# BMS029B_PinConfig.net
KiCad netlist of a schematic drawn in Altium Designer
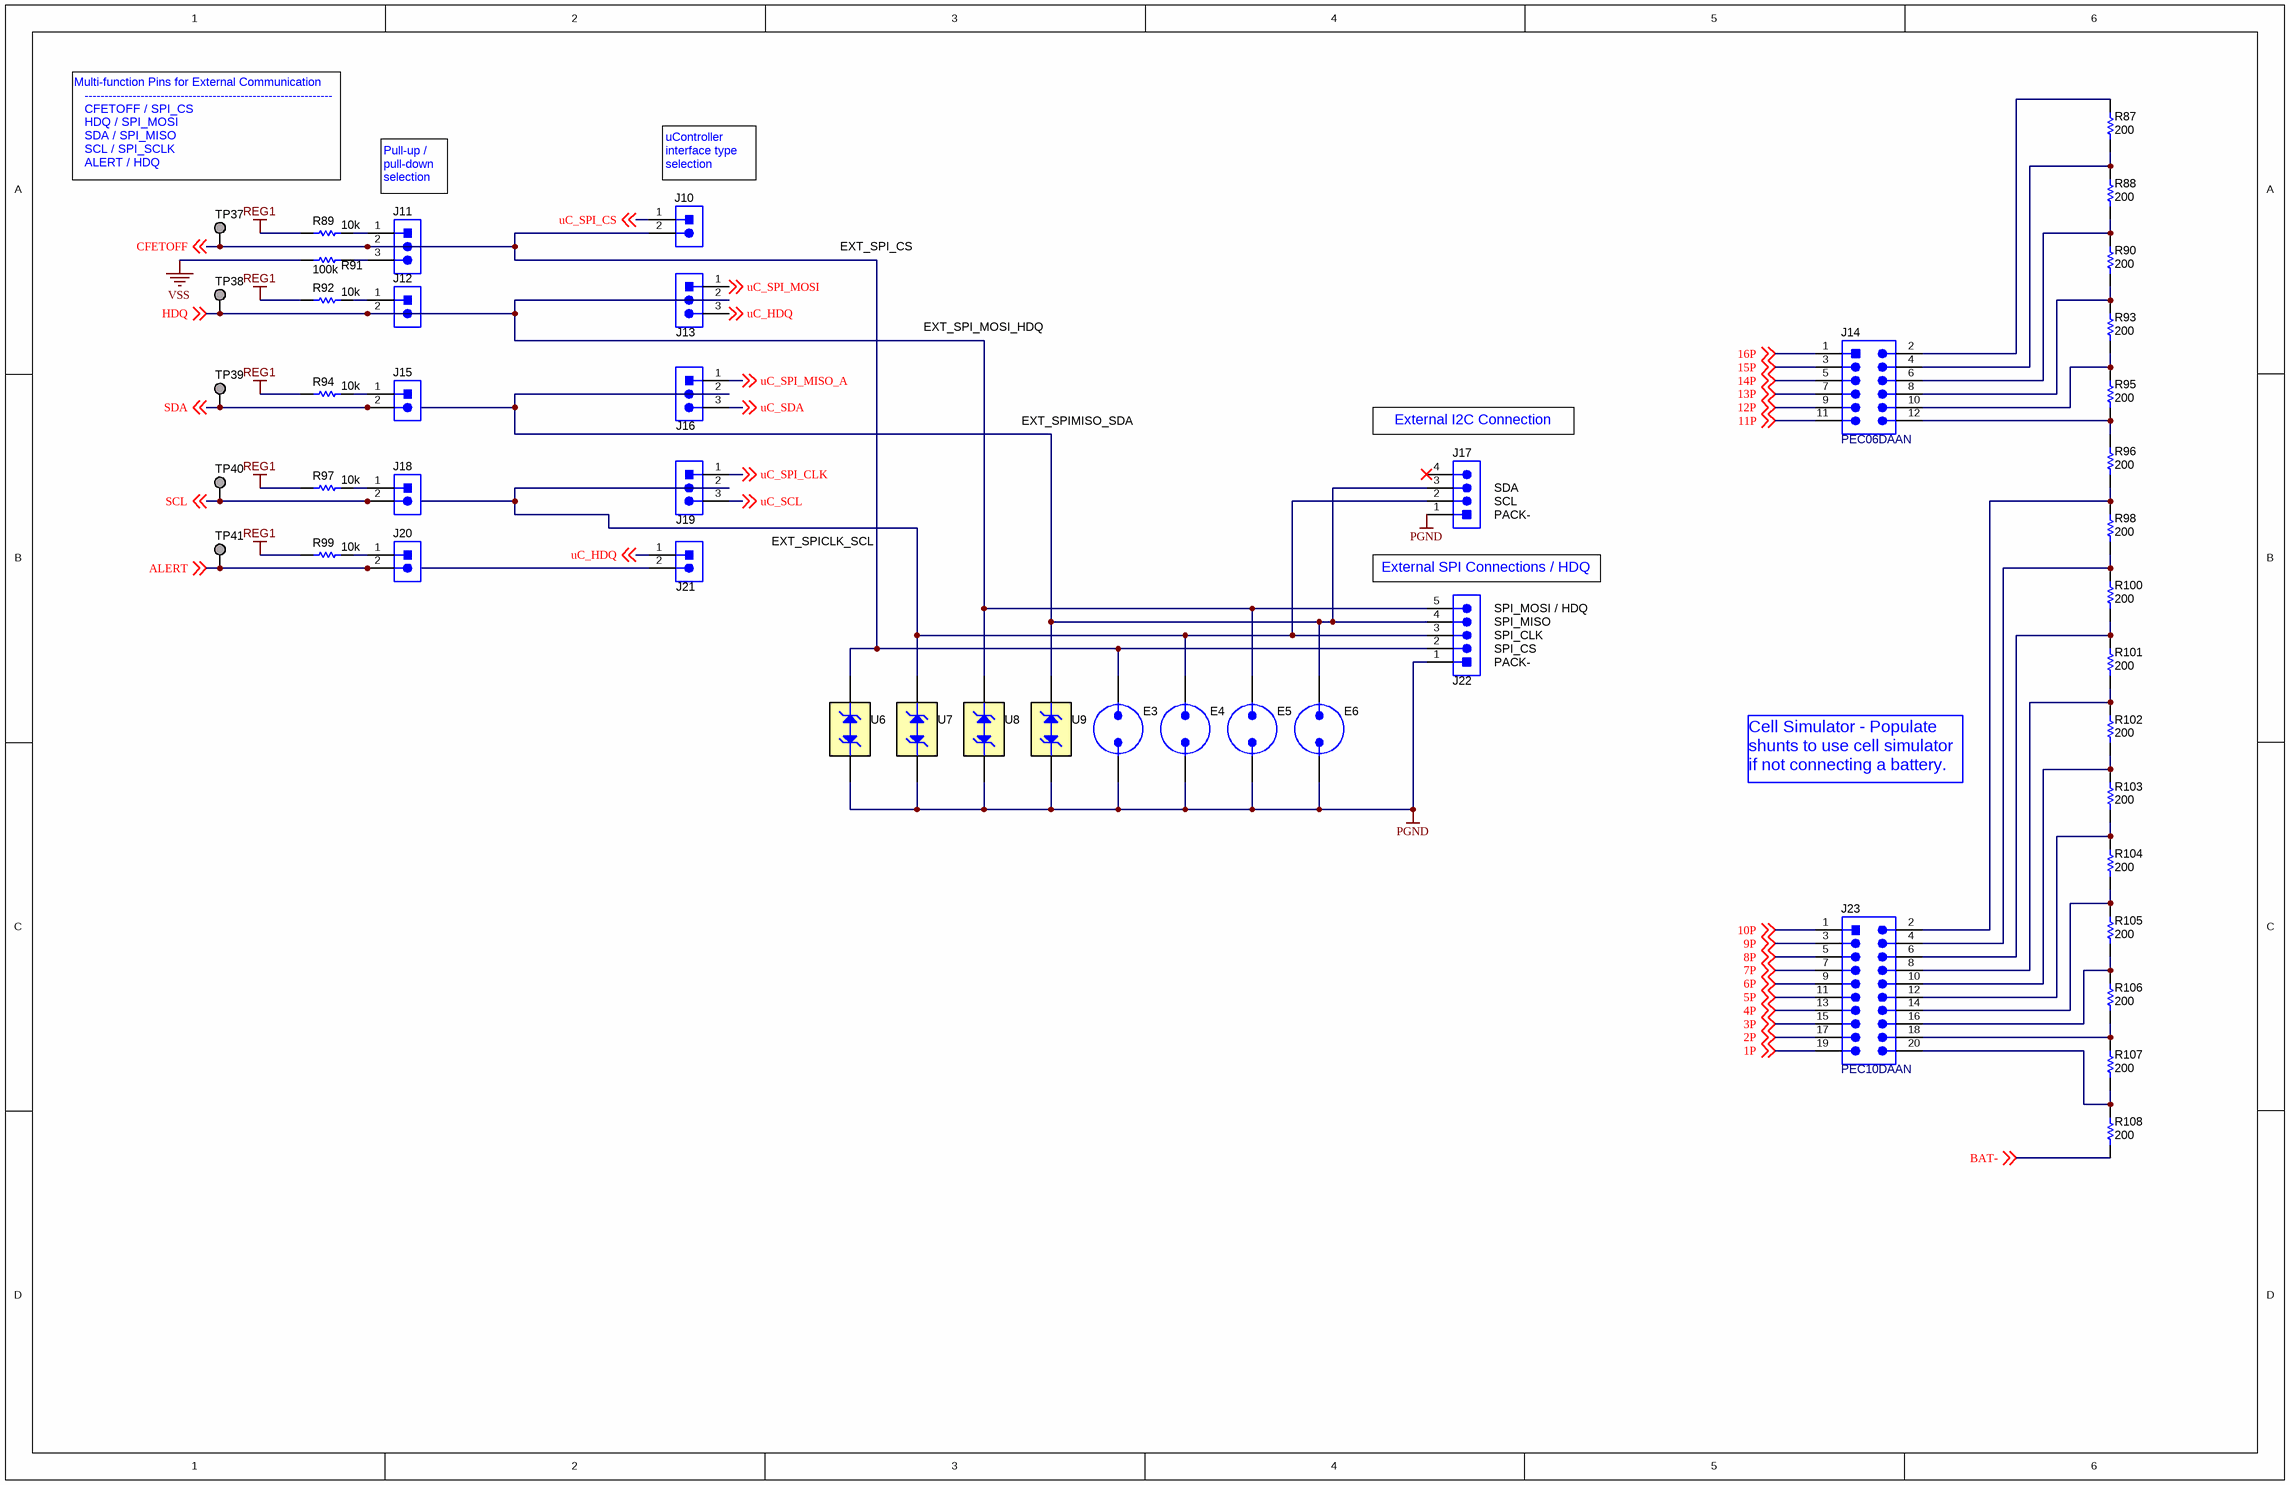
[diagram p0: BMS029B_PinConfig.SchDoc]

(export (version "E")
  (design (tool "Eeschema 10.0.6"))
  (components
    (comp (ref "E3")
      (value "Spark Gap")
      (footprint "SPARK_GAP2")
      (libsource (lib "Altium Vault - TI") (part "CMP-0079939-1"))
    )
    (comp (ref "E4")
      (value "Spark Gap")
      (footprint "SPARK_GAP2")
      (libsource (lib "Altium Vault - TI") (part "CMP-0079939-1"))
    )
    (comp (ref "E5")
      (value "Spark Gap")
      (footprint "SPARK_GAP2")
      (libsource (lib "Altium Vault - TI") (part "CMP-0079939-1"))
    )
    (comp (ref "E6")
      (value "Spark Gap")
      (footprint "SPARK_GAP2")
      (libsource (lib "Altium Vault - TI") (part "CMP-0079939-1"))
    )
    (comp (ref "J10")
      (value "PEC02SAAN")
      (footprint "CONN_PEC02SAAN")
      (description "Header, 100mil, 2x1, Tin, TH")
      (fields
        (field (name "MANUFACTURER") "Sullins Connector Solutions")
        (field (name "PUBLISHER") "Texas Instruments")
      )
      (libsource (lib "Altium Vault - TI") (part "Header_2x1"))
    )
    (comp (ref "J11")
      (value "87898-0304")
      (footprint "Molex_87898-0304")
      (description "Header, 2.54mm, 3x1, Gold, SMT")
      (fields (field (name "MANUFACTURER") "Molex") (field (name "PUBLISHER") "Texas Instruments"))
      (libsource (lib "") (part "CMP-0075388-1_1"))
    )
    (comp (ref "J12")
      (value "PEC02SAAN")
      (footprint "CONN_PEC02SAAN")
      (description "Header, 100mil, 2x1, Tin, TH")
      (fields
        (field (name "MANUFACTURER") "Sullins Connector Solutions")
        (field (name "PUBLISHER") "Texas Instruments")
      )
      (libsource (lib "Altium Vault - TI") (part "Header_2x1"))
    )
    (comp (ref "J13")
      (value "87898-0304")
      (footprint "Molex_87898-0304")
      (description "Header, 2.54mm, 3x1, Gold, SMT")
      (fields (field (name "MANUFACTURER") "Molex") (field (name "PUBLISHER") "Texas Instruments"))
      (libsource (lib "Altium Vault - TI") (part "CMP-0075388-1"))
    )
    (comp (ref "J14")
      (value "PEC06DAAN")
      (footprint "CONN_PEC06DAAN")
      (description "Header, 100mil, 6x2, Tin, TH")
      (fields (field (name "MANUFACTURER") "Sullins Connector Solutions"))
      (libsource (lib "Altium Vault - TI") (part "Header_6x2"))
    )
    (comp (ref "J15")
      (value "PEC02SAAN")
      (footprint "CONN_PEC02SAAN")
      (description "Header, 100mil, 2x1, Tin, TH")
      (fields
        (field (name "MANUFACTURER") "Sullins Connector Solutions")
        (field (name "PUBLISHER") "Texas Instruments")
      )
      (libsource (lib "Altium Vault - TI") (part "Header_2x1"))
    )
    (comp (ref "J16")
      (value "87898-0304")
      (footprint "Molex_87898-0304")
      (description "Header, 2.54mm, 3x1, Gold, SMT")
      (fields (field (name "MANUFACTURER") "Molex") (field (name "PUBLISHER") "Texas Instruments"))
      (libsource (lib "Altium Vault - TI") (part "CMP-0075388-1"))
    )
    (comp (ref "J17")
      (value "22/05/3041")
      (footprint "CONN_22-05-3041")
      (description "Header (friction lock), 100mil, 4x1, R/A, TH")
      (fields (field (name "MANUFACTURER") "Molex") (field (name "PUBLISHER") "Texas Instruments"))
      (libsource (lib "Altium Vault - TI") (part "CMP-0055187-1"))
    )
    (comp (ref "J18")
      (value "PEC02SAAN")
      (footprint "CONN_PEC02SAAN")
      (description "Header, 100mil, 2x1, Tin, TH")
      (fields
        (field (name "MANUFACTURER") "Sullins Connector Solutions")
        (field (name "PUBLISHER") "Texas Instruments")
      )
      (libsource (lib "Altium Vault - TI") (part "Header_2x1"))
    )
    (comp (ref "J19")
      (value "87898-0304")
      (footprint "Molex_87898-0304")
      (description "Header, 2.54mm, 3x1, Gold, SMT")
      (fields (field (name "MANUFACTURER") "Molex") (field (name "PUBLISHER") "Texas Instruments"))
      (libsource (lib "Altium Vault - TI") (part "CMP-0075388-1"))
    )
    (comp (ref "J20")
      (value "PEC02SAAN")
      (footprint "CONN_PEC02SAAN")
      (description "Header, 100mil, 2x1, Tin, TH")
      (fields
        (field (name "MANUFACTURER") "Sullins Connector Solutions")
        (field (name "PUBLISHER") "Texas Instruments")
      )
      (libsource (lib "Altium Vault - TI") (part "Header_2x1"))
    )
    (comp (ref "J21")
      (value "PEC02SAAN")
      (footprint "CONN_PEC02SAAN")
      (description "Header, 100mil, 2x1, Tin, TH")
      (fields
        (field (name "MANUFACTURER") "Sullins Connector Solutions")
        (field (name "PUBLISHER") "Texas Instruments")
      )
      (libsource (lib "Altium Vault - TI") (part "Header_2x1"))
    )
    (comp (ref "J22")
      (value "PEC05SAAN")
      (footprint "Sullins_PxC05SAAN")
      (description "Header, 2.54mm, 5x1, Tin, TH")
      (fields
        (field (name "MANUFACTURER") "Sullins Connector Solutions")
        (field (name "PUBLISHER") "Texas Instruments")
      )
      (libsource (lib "Altium Vault - TI") (part "CMP-0054597-1"))
    )
    (comp (ref "J23")
      (value "PEC10DAAN")
      (footprint "SULLINS_PEC10DAAN")
      (description "Header, 2.54mm, 10x2, Tin, TH")
      (fields (field (name "MANUFACTURER") "Sullins Connector Solutions"))
      (libsource (lib "Altium Vault - TI") (part "Header_10x2"))
    )
    (comp (ref "R87")
      (value "CRCW1206200RFKEA")
      (footprint "1206")
      (description "RES, 200, 1%, 0.25 W, AEC-Q200 Grade 0, 1206")
      (fields (field (name "MANUFACTURER") "Vishay-Dale") (field (name "VALUEDISPLAYED") "200"))
      (libsource (lib "Altium Vault - TI") (part "Resistor"))
    )
    (comp (ref "R88")
      (value "CRCW1206200RFKEA")
      (footprint "1206")
      (description "RES, 200, 1%, 0.25 W, AEC-Q200 Grade 0, 1206")
      (fields (field (name "MANUFACTURER") "Vishay-Dale") (field (name "VALUEDISPLAYED") "200"))
      (libsource (lib "Altium Vault - TI") (part "Resistor"))
    )
    (comp (ref "R89")
      (value "CRCW060310K0JNEA")
      (footprint "0603")
      (description "RES, 10 k, 5%, 0.1 W, AEC-Q200 Grade 0, 0603")
      (fields (field (name "MANUFACTURER") "Vishay-Dale") (field (name "VALUEDISPLAYED") "10k"))
      (libsource (lib "Altium Vault - TI") (part "CMP-0025701-4"))
    )
    (comp (ref "R90")
      (value "CRCW1206200RFKEA")
      (footprint "1206")
      (description "RES, 200, 1%, 0.25 W, AEC-Q200 Grade 0, 1206")
      (fields (field (name "MANUFACTURER") "Vishay-Dale") (field (name "VALUEDISPLAYED") "200"))
      (libsource (lib "Altium Vault - TI") (part "Resistor"))
    )
    (comp (ref "R91")
      (value "CRCW0603100KJNEA")
      (footprint "0603")
      (description "RES, 100 k, 5%, 0.1 W, AEC-Q200 Grade 0, 0603")
      (fields (field (name "MANUFACTURER") "Vishay-Dale") (field (name "VALUEDISPLAYED") "100k"))
      (libsource (lib "Altium Vault - TI") (part "Resistor"))
    )
    (comp (ref "R92")
      (value "CRCW060310K0JNEA")
      (footprint "0603")
      (description "RES, 10 k, 5%, 0.1 W, AEC-Q200 Grade 0, 0603")
      (fields (field (name "MANUFACTURER") "Vishay-Dale") (field (name "VALUEDISPLAYED") "10k"))
      (libsource (lib "Altium Vault - TI") (part "CMP-0025701-4"))
    )
    (comp (ref "R93")
      (value "CRCW1206200RFKEA")
      (footprint "1206")
      (description "RES, 200, 1%, 0.25 W, AEC-Q200 Grade 0, 1206")
      (fields (field (name "MANUFACTURER") "Vishay-Dale") (field (name "VALUEDISPLAYED") "200"))
      (libsource (lib "Altium Vault - TI") (part "Resistor"))
    )
    (comp (ref "R94")
      (value "CRCW060310K0JNEA")
      (footprint "0603")
      (description "RES, 10 k, 5%, 0.1 W, AEC-Q200 Grade 0, 0603")
      (fields (field (name "MANUFACTURER") "Vishay-Dale") (field (name "VALUEDISPLAYED") "10k"))
      (libsource (lib "Altium Vault - TI") (part "CMP-0025701-4"))
    )
    (comp (ref "R95")
      (value "CRCW1206200RFKEA")
      (footprint "1206")
      (description "RES, 200, 1%, 0.25 W, AEC-Q200 Grade 0, 1206")
      (fields (field (name "MANUFACTURER") "Vishay-Dale") (field (name "VALUEDISPLAYED") "200"))
      (libsource (lib "Altium Vault - TI") (part "Resistor"))
    )
    (comp (ref "R96")
      (value "CRCW1206200RFKEA")
      (footprint "1206")
      (description "RES, 200, 1%, 0.25 W, AEC-Q200 Grade 0, 1206")
      (fields (field (name "MANUFACTURER") "Vishay-Dale") (field (name "VALUEDISPLAYED") "200"))
      (libsource (lib "Altium Vault - TI") (part "Resistor"))
    )
    (comp (ref "R97")
      (value "CRCW060310K0JNEA")
      (footprint "0603")
      (description "RES, 10 k, 5%, 0.1 W, AEC-Q200 Grade 0, 0603")
      (fields (field (name "MANUFACTURER") "Vishay-Dale") (field (name "VALUEDISPLAYED") "10k"))
      (libsource (lib "Altium Vault - TI") (part "CMP-0025701-4"))
    )
    (comp (ref "R98")
      (value "CRCW1206200RFKEA")
      (footprint "1206")
      (description "RES, 200, 1%, 0.25 W, AEC-Q200 Grade 0, 1206")
      (fields (field (name "MANUFACTURER") "Vishay-Dale") (field (name "VALUEDISPLAYED") "200"))
      (libsource (lib "Altium Vault - TI") (part "Resistor"))
    )
    (comp (ref "R99")
      (value "CRCW060310K0JNEA")
      (footprint "0603")
      (description "RES, 10 k, 5%, 0.1 W, AEC-Q200 Grade 0, 0603")
      (fields (field (name "MANUFACTURER") "Vishay-Dale") (field (name "VALUEDISPLAYED") "10k"))
      (libsource (lib "Altium Vault - TI") (part "CMP-0025701-4"))
    )
    (comp (ref "R100")
      (value "CRCW1206200RFKEA")
      (footprint "1206")
      (description "RES, 200, 1%, 0.25 W, AEC-Q200 Grade 0, 1206")
      (fields (field (name "MANUFACTURER") "Vishay-Dale") (field (name "VALUEDISPLAYED") "200"))
      (libsource (lib "Altium Vault - TI") (part "Resistor"))
    )
    (comp (ref "R101")
      (value "CRCW1206200RFKEA")
      (footprint "1206")
      (description "RES, 200, 1%, 0.25 W, AEC-Q200 Grade 0, 1206")
      (fields (field (name "MANUFACTURER") "Vishay-Dale") (field (name "VALUEDISPLAYED") "200"))
      (libsource (lib "Altium Vault - TI") (part "Resistor"))
    )
    (comp (ref "R102")
      (value "CRCW1206200RFKEA")
      (footprint "1206")
      (description "RES, 200, 1%, 0.25 W, AEC-Q200 Grade 0, 1206")
      (fields (field (name "MANUFACTURER") "Vishay-Dale") (field (name "VALUEDISPLAYED") "200"))
      (libsource (lib "Altium Vault - TI") (part "Resistor"))
    )
    (comp (ref "R103")
      (value "CRCW1206200RFKEA")
      (footprint "1206")
      (description "RES, 200, 1%, 0.25 W, AEC-Q200 Grade 0, 1206")
      (fields (field (name "MANUFACTURER") "Vishay-Dale") (field (name "VALUEDISPLAYED") "200"))
      (libsource (lib "Altium Vault - TI") (part "Resistor"))
    )
    (comp (ref "R104")
      (value "CRCW1206200RFKEA")
      (footprint "1206")
      (description "RES, 200, 1%, 0.25 W, AEC-Q200 Grade 0, 1206")
      (fields (field (name "MANUFACTURER") "Vishay-Dale") (field (name "VALUEDISPLAYED") "200"))
      (libsource (lib "Altium Vault - TI") (part "Resistor"))
    )
    (comp (ref "R105")
      (value "CRCW1206200RFKEA")
      (footprint "1206")
      (description "RES, 200, 1%, 0.25 W, AEC-Q200 Grade 0, 1206")
      (fields (field (name "MANUFACTURER") "Vishay-Dale") (field (name "VALUEDISPLAYED") "200"))
      (libsource (lib "Altium Vault - TI") (part "Resistor"))
    )
    (comp (ref "R106")
      (value "CRCW1206200RFKEA")
      (footprint "1206")
      (description "RES, 200, 1%, 0.25 W, AEC-Q200 Grade 0, 1206")
      (fields (field (name "MANUFACTURER") "Vishay-Dale") (field (name "VALUEDISPLAYED") "200"))
      (libsource (lib "Altium Vault - TI") (part "Resistor"))
    )
    (comp (ref "R107")
      (value "CRCW1206200RFKEA")
      (footprint "1206")
      (description "RES, 200, 1%, 0.25 W, AEC-Q200 Grade 0, 1206")
      (fields (field (name "MANUFACTURER") "Vishay-Dale") (field (name "VALUEDISPLAYED") "200"))
      (libsource (lib "Altium Vault - TI") (part "Resistor"))
    )
    (comp (ref "R108")
      (value "CRCW1206200RFKEA")
      (footprint "1206")
      (description "RES, 200, 1%, 0.25 W, AEC-Q200 Grade 0, 1206")
      (fields (field (name "MANUFACTURER") "Vishay-Dale") (field (name "VALUEDISPLAYED") "200"))
      (libsource (lib "Altium Vault - TI") (part "Resistor"))
    )
    (comp (ref "TP37")
      (value "TESTPOINT")
      (footprint "TP_50MIL-25MILHOLE")
      (description "TEST POINT.  No entry in BOM.")
      (libsource (lib "Altium Vault - TI") (part "TESTPOINT"))
    )
    (comp (ref "TP38")
      (value "TESTPOINT")
      (footprint "TP_50MIL-25MILHOLE")
      (description "TEST POINT.  No entry in BOM.")
      (libsource (lib "Altium Vault - TI") (part "TESTPOINT"))
    )
    (comp (ref "TP39")
      (value "TESTPOINT")
      (footprint "TP_50MIL-25MILHOLE")
      (description "TEST POINT.  No entry in BOM.")
      (libsource (lib "Altium Vault - TI") (part "TESTPOINT"))
    )
    (comp (ref "TP40")
      (value "TESTPOINT")
      (footprint "TP_50MIL-25MILHOLE")
      (description "TEST POINT.  No entry in BOM.")
      (libsource (lib "Altium Vault - TI") (part "TESTPOINT"))
    )
    (comp (ref "TP41")
      (value "TESTPOINT")
      (footprint "TP_50MIL-25MILHOLE")
      (description "TEST POINT.  No entry in BOM.")
      (libsource (lib "Altium Vault - TI") (part "TESTPOINT"))
    )
    (comp (ref "U6")
      (value "TPD1E10B06DPYR")
      (footprint "DPY0002A")
      (description "Single-Channel ESD in 0402 Package With 10pF Capacitance and 6V Breakdown, DPY0002A (X1SON-2)")
      (fields
        (field (name "MANUFACTURER") "Texas Instruments")
        (field (name "ALTERNATE PARTNUMBER") "TPD1E10B06DPYT")
      )
      (libsource (lib "Altium Vault - TI") (part "TPD1E10B06"))
    )
    (comp (ref "U7")
      (value "TPD1E10B06DPYR")
      (footprint "DPY0002A")
      (description "Single-Channel ESD in 0402 Package With 10pF Capacitance and 6V Breakdown, DPY0002A (X1SON-2)")
      (fields
        (field (name "MANUFACTURER") "Texas Instruments")
        (field (name "ALTERNATE PARTNUMBER") "TPD1E10B06DPYT")
      )
      (libsource (lib "Altium Vault - TI") (part "TPD1E10B06"))
    )
    (comp (ref "U8")
      (value "TPD1E10B06DPYR")
      (footprint "DPY0002A")
      (description "Single-Channel ESD in 0402 Package With 10pF Capacitance and 6V Breakdown, DPY0002A (X1SON-2)")
      (fields
        (field (name "MANUFACTURER") "Texas Instruments")
        (field (name "ALTERNATE PARTNUMBER") "TPD1E10B06DPYT")
      )
      (libsource (lib "Altium Vault - TI") (part "TPD1E10B06"))
    )
    (comp (ref "U9")
      (value "TPD1E10B06DPYR")
      (footprint "DPY0002A")
      (description "Single-Channel ESD in 0402 Package With 10pF Capacitance and 6V Breakdown, DPY0002A (X1SON-2)")
      (fields
        (field (name "MANUFACTURER") "Texas Instruments")
        (field (name "ALTERNATE PARTNUMBER") "TPD1E10B06DPYT")
      )
      (libsource (lib "Altium Vault - TI") (part "TPD1E10B06"))
    )
  )
  (nets
    (net (code "1") (name "1P") (class "Default")
      (node (ref "J23") (pin "19") (pinfunction "19_19") (pintype "passive"))
    )
    (net (code "2") (name "2P") (class "Default")
      (node (ref "J23") (pin "17") (pinfunction "17_17") (pintype "passive"))
    )
    (net (code "3") (name "3P") (class "Default")
      (node (ref "J23") (pin "15") (pinfunction "15_15") (pintype "passive"))
    )
    (net (code "4") (name "4P") (class "Default")
      (node (ref "J23") (pin "13") (pinfunction "13_13") (pintype "passive"))
    )
    (net (code "5") (name "5P") (class "Default")
      (node (ref "J23") (pin "11") (pinfunction "11_11") (pintype "passive"))
    )
    (net (code "6") (name "6P") (class "Default")
      (node (ref "J23") (pin "9") (pinfunction "9_9") (pintype "passive"))
    )
    (net (code "7") (name "7P") (class "Default")
      (node (ref "J23") (pin "7") (pinfunction "7_7") (pintype "passive"))
    )
    (net (code "8") (name "8P") (class "Default")
      (node (ref "J23") (pin "5") (pinfunction "5_5") (pintype "passive"))
    )
    (net (code "9") (name "9P") (class "Default")
      (node (ref "J23") (pin "3") (pinfunction "3_3") (pintype "passive"))
    )
    (net (code "10") (name "10P") (class "Default")
      (node (ref "J23") (pin "1") (pinfunction "1_1") (pintype "passive"))
    )
    (net (code "11") (name "11P") (class "Default")
      (node (ref "J14") (pin "11") (pinfunction "11_11") (pintype "passive"))
    )
    (net (code "12") (name "12P") (class "Default")
      (node (ref "J14") (pin "9") (pinfunction "9_9") (pintype "passive"))
    )
    (net (code "13") (name "13P") (class "Default")
      (node (ref "J14") (pin "7") (pinfunction "7_7") (pintype "passive"))
    )
    (net (code "14") (name "14P") (class "Default")
      (node (ref "J14") (pin "5") (pinfunction "5_5") (pintype "passive"))
    )
    (net (code "15") (name "15P") (class "Default")
      (node (ref "J14") (pin "3") (pinfunction "3_3") (pintype "passive"))
    )
    (net (code "16") (name "16P") (class "Default")
      (node (ref "J14") (pin "1") (pinfunction "1_1") (pintype "passive"))
    )
    (net (code "17") (name "ALERT") (class "Default")
      (node (ref "J20") (pin "2") (pinfunction "2_2") (pintype "passive"))
      (node (ref "J21") (pin "2") (pinfunction "2_2") (pintype "passive"))
      (node (ref "TP41") (pin "1") (pintype "passive"))
    )
    (net (code "18") (name "BAT-") (class "Default")
      (node (ref "R108") (pin "1") (pinfunction "1_1") (pintype "passive"))
    )
    (net (code "19") (name "CFETOFF") (class "Default")
      (node (ref "E3") (pin "1") (pinfunction "1_1") (pintype "passive"))
      (node (ref "J10") (pin "2") (pinfunction "2_2") (pintype "passive"))
      (node (ref "J11") (pin "2") (pinfunction "2_2") (pintype "passive"))
      (node (ref "J22") (pin "2") (pinfunction "2_2") (pintype "passive"))
      (node (ref "TP37") (pin "1") (pintype "passive"))
      (node (ref "U6") (pin "1") (pinfunction "K_1") (pintype "passive"))
    )
    (net (code "20") (name "HDQ") (class "Default")
      (node (ref "E5") (pin "1") (pinfunction "1_1") (pintype "passive"))
      (node (ref "J12") (pin "2") (pinfunction "2_2") (pintype "passive"))
      (node (ref "J13") (pin "2") (pinfunction "2_2") (pintype "passive"))
      (node (ref "J22") (pin "5") (pinfunction "5_5") (pintype "passive"))
      (node (ref "TP38") (pin "1") (pintype "passive"))
      (node (ref "U8") (pin "1") (pinfunction "K_1") (pintype "passive"))
    )
    (net (code "21") (name "Net-(J11-Pad1)") (class "Default")
      (node (ref "J11") (pin "1") (pinfunction "1_1") (pintype "passive"))
      (node (ref "R89") (pin "2") (pinfunction "2_2") (pintype "passive"))
    )
    (net (code "22") (name "Net-(J11-Pad3)") (class "Default")
      (node (ref "J11") (pin "3") (pinfunction "3_3") (pintype "passive"))
      (node (ref "R91") (pin "2") (pinfunction "2_2") (pintype "passive"))
    )
    (net (code "23") (name "Net-(J12-Pad1)") (class "Default")
      (node (ref "J12") (pin "1") (pinfunction "1_1") (pintype "passive"))
      (node (ref "R92") (pin "2") (pinfunction "2_2") (pintype "passive"))
    )
    (net (code "24") (name "Net-(J14-Pad2)") (class "Default")
      (node (ref "J14") (pin "2") (pinfunction "2_2") (pintype "passive"))
      (node (ref "R87") (pin "2") (pinfunction "2_2") (pintype "passive"))
    )
    (net (code "25") (name "Net-(J14-Pad4)") (class "Default")
      (node (ref "J14") (pin "4") (pinfunction "4_4") (pintype "passive"))
      (node (ref "R87") (pin "1") (pinfunction "1_1") (pintype "passive"))
      (node (ref "R88") (pin "2") (pinfunction "2_2") (pintype "passive"))
    )
    (net (code "26") (name "Net-(J14-Pad6)") (class "Default")
      (node (ref "J14") (pin "6") (pinfunction "6_6") (pintype "passive"))
      (node (ref "R88") (pin "1") (pinfunction "1_1") (pintype "passive"))
      (node (ref "R90") (pin "2") (pinfunction "2_2") (pintype "passive"))
    )
    (net (code "27") (name "Net-(J14-Pad8)") (class "Default")
      (node (ref "J14") (pin "8") (pinfunction "8_8") (pintype "passive"))
      (node (ref "R90") (pin "1") (pinfunction "1_1") (pintype "passive"))
      (node (ref "R93") (pin "2") (pinfunction "2_2") (pintype "passive"))
    )
    (net (code "28") (name "Net-(J14-Pad10)") (class "Default")
      (node (ref "J14") (pin "10") (pinfunction "10_10") (pintype "passive"))
      (node (ref "R93") (pin "1") (pinfunction "1_1") (pintype "passive"))
      (node (ref "R95") (pin "2") (pinfunction "2_2") (pintype "passive"))
    )
    (net (code "29") (name "Net-(J14-Pad12)") (class "Default")
      (node (ref "J14") (pin "12") (pinfunction "12_12") (pintype "passive"))
      (node (ref "R95") (pin "1") (pinfunction "1_1") (pintype "passive"))
      (node (ref "R96") (pin "2") (pinfunction "2_2") (pintype "passive"))
    )
    (net (code "30") (name "Net-(J15-Pad1)") (class "Default")
      (node (ref "J15") (pin "1") (pinfunction "1_1") (pintype "passive"))
      (node (ref "R94") (pin "2") (pinfunction "2_2") (pintype "passive"))
    )
    (net (code "31") (name "Net-(J18-Pad1)") (class "Default")
      (node (ref "J18") (pin "1") (pinfunction "1_1") (pintype "passive"))
      (node (ref "R97") (pin "2") (pinfunction "2_2") (pintype "passive"))
    )
    (net (code "32") (name "Net-(J20-Pad1)") (class "Default")
      (node (ref "J20") (pin "1") (pinfunction "1_1") (pintype "passive"))
      (node (ref "R99") (pin "2") (pinfunction "2_2") (pintype "passive"))
    )
    (net (code "33") (name "Net-(J23-Pad2)") (class "Default")
      (node (ref "J23") (pin "2") (pinfunction "2_2") (pintype "passive"))
      (node (ref "R96") (pin "1") (pinfunction "1_1") (pintype "passive"))
      (node (ref "R98") (pin "2") (pinfunction "2_2") (pintype "passive"))
    )
    (net (code "34") (name "Net-(J23-Pad4)") (class "Default")
      (node (ref "J23") (pin "4") (pinfunction "4_4") (pintype "passive"))
      (node (ref "R100") (pin "2") (pinfunction "2_2") (pintype "passive"))
      (node (ref "R98") (pin "1") (pinfunction "1_1") (pintype "passive"))
    )
    (net (code "35") (name "Net-(J23-Pad6)") (class "Default")
      (node (ref "J23") (pin "6") (pinfunction "6_6") (pintype "passive"))
      (node (ref "R100") (pin "1") (pinfunction "1_1") (pintype "passive"))
      (node (ref "R101") (pin "2") (pinfunction "2_2") (pintype "passive"))
    )
    (net (code "36") (name "Net-(J23-Pad8)") (class "Default")
      (node (ref "J23") (pin "8") (pinfunction "8_8") (pintype "passive"))
      (node (ref "R101") (pin "1") (pinfunction "1_1") (pintype "passive"))
      (node (ref "R102") (pin "2") (pinfunction "2_2") (pintype "passive"))
    )
    (net (code "37") (name "Net-(J23-Pad10)") (class "Default")
      (node (ref "J23") (pin "10") (pinfunction "10_10") (pintype "passive"))
      (node (ref "R102") (pin "1") (pinfunction "1_1") (pintype "passive"))
      (node (ref "R103") (pin "2") (pinfunction "2_2") (pintype "passive"))
    )
    (net (code "38") (name "Net-(J23-Pad12)") (class "Default")
      (node (ref "J23") (pin "12") (pinfunction "12_12") (pintype "passive"))
      (node (ref "R103") (pin "1") (pinfunction "1_1") (pintype "passive"))
      (node (ref "R104") (pin "2") (pinfunction "2_2") (pintype "passive"))
    )
    (net (code "39") (name "Net-(J23-Pad14)") (class "Default")
      (node (ref "J23") (pin "14") (pinfunction "14_14") (pintype "passive"))
      (node (ref "R104") (pin "1") (pinfunction "1_1") (pintype "passive"))
      (node (ref "R105") (pin "2") (pinfunction "2_2") (pintype "passive"))
    )
    (net (code "40") (name "Net-(J23-Pad16)") (class "Default")
      (node (ref "J23") (pin "16") (pinfunction "16_16") (pintype "passive"))
      (node (ref "R105") (pin "1") (pinfunction "1_1") (pintype "passive"))
      (node (ref "R106") (pin "2") (pinfunction "2_2") (pintype "passive"))
    )
    (net (code "41") (name "Net-(J23-Pad18)") (class "Default")
      (node (ref "J23") (pin "18") (pinfunction "18_18") (pintype "passive"))
      (node (ref "R106") (pin "1") (pinfunction "1_1") (pintype "passive"))
      (node (ref "R107") (pin "2") (pinfunction "2_2") (pintype "passive"))
    )
    (net (code "42") (name "Net-(J23-Pad20)") (class "Default")
      (node (ref "J23") (pin "20") (pinfunction "20_20") (pintype "passive"))
      (node (ref "R107") (pin "1") (pinfunction "1_1") (pintype "passive"))
      (node (ref "R108") (pin "2") (pinfunction "2_2") (pintype "passive"))
    )
    (net (code "43") (name "PGND") (class "Default")
      (node (ref "E3") (pin "2") (pinfunction "2_2") (pintype "passive"))
      (node (ref "E4") (pin "2") (pinfunction "2_2") (pintype "passive"))
      (node (ref "E5") (pin "2") (pinfunction "2_2") (pintype "passive"))
      (node (ref "E6") (pin "2") (pinfunction "2_2") (pintype "passive"))
      (node (ref "J17") (pin "1") (pinfunction "1_1") (pintype "passive"))
      (node (ref "J22") (pin "1") (pinfunction "1_1") (pintype "passive"))
      (node (ref "U6") (pin "2") (pinfunction "A_2") (pintype "passive"))
      (node (ref "U7") (pin "2") (pinfunction "A_2") (pintype "passive"))
      (node (ref "U8") (pin "2") (pinfunction "A_2") (pintype "passive"))
      (node (ref "U9") (pin "2") (pinfunction "A_2") (pintype "passive"))
    )
    (net (code "44") (name "REG1") (class "Default")
      (node (ref "R89") (pin "1") (pinfunction "1_1") (pintype "passive"))
      (node (ref "R92") (pin "1") (pinfunction "1_1") (pintype "passive"))
      (node (ref "R94") (pin "1") (pinfunction "1_1") (pintype "passive"))
      (node (ref "R97") (pin "1") (pinfunction "1_1") (pintype "passive"))
      (node (ref "R99") (pin "1") (pinfunction "1_1") (pintype "passive"))
    )
    (net (code "45") (name "SCL") (class "Default")
      (node (ref "E4") (pin "1") (pinfunction "1_1") (pintype "passive"))
      (node (ref "J17") (pin "2") (pinfunction "2_2") (pintype "passive"))
      (node (ref "J18") (pin "2") (pinfunction "2_2") (pintype "passive"))
      (node (ref "J19") (pin "2") (pinfunction "2_2") (pintype "passive"))
      (node (ref "J22") (pin "3") (pinfunction "3_3") (pintype "passive"))
      (node (ref "TP40") (pin "1") (pintype "passive"))
      (node (ref "U7") (pin "1") (pinfunction "K_1") (pintype "passive"))
    )
    (net (code "46") (name "SDA") (class "Default")
      (node (ref "E6") (pin "1") (pinfunction "1_1") (pintype "passive"))
      (node (ref "J15") (pin "2") (pinfunction "2_2") (pintype "passive"))
      (node (ref "J16") (pin "2") (pinfunction "2_2") (pintype "passive"))
      (node (ref "J17") (pin "3") (pinfunction "3_3") (pintype "passive"))
      (node (ref "J22") (pin "4") (pinfunction "4_4") (pintype "passive"))
      (node (ref "TP39") (pin "1") (pintype "passive"))
      (node (ref "U9") (pin "1") (pinfunction "K_1") (pintype "passive"))
    )
    (net (code "47") (name "VSS") (class "Default")
      (node (ref "R91") (pin "1") (pinfunction "1_1") (pintype "passive"))
    )
    (net (code "48") (name "uC_HDQ") (class "Default")
      (node (ref "J13") (pin "3") (pinfunction "3_3") (pintype "passive"))
      (node (ref "J21") (pin "1") (pinfunction "1_1") (pintype "passive"))
    )
    (net (code "49") (name "uC_SCL") (class "Default")
      (node (ref "J19") (pin "3") (pinfunction "3_3") (pintype "passive"))
    )
    (net (code "50") (name "uC_SDA") (class "Default")
      (node (ref "J16") (pin "3") (pinfunction "3_3") (pintype "passive"))
    )
    (net (code "51") (name "uC_SPI_CLK") (class "Default")
      (node (ref "J19") (pin "1") (pinfunction "1_1") (pintype "passive"))
    )
    (net (code "52") (name "uC_SPI_CS") (class "Default")
      (node (ref "J10") (pin "1") (pinfunction "1_1") (pintype "passive"))
    )
    (net (code "53") (name "uC_SPI_MISO_A") (class "Default")
      (node (ref "J16") (pin "1") (pinfunction "1_1") (pintype "passive"))
    )
    (net (code "54") (name "uC_SPI_MOSI") (class "Default")
      (node (ref "J13") (pin "1") (pinfunction "1_1") (pintype "passive"))
    )
    (net (code "55") (name "unconnected-(J17-Pad4)") (class "Default")
      (node (ref "J17") (pin "4") (pinfunction "4_4") (pintype "passive+no_connect"))
    )
  )
)
